# transistor_dc_motor_driver.net
KiCad netlist of a schematic drawn in EAGLE
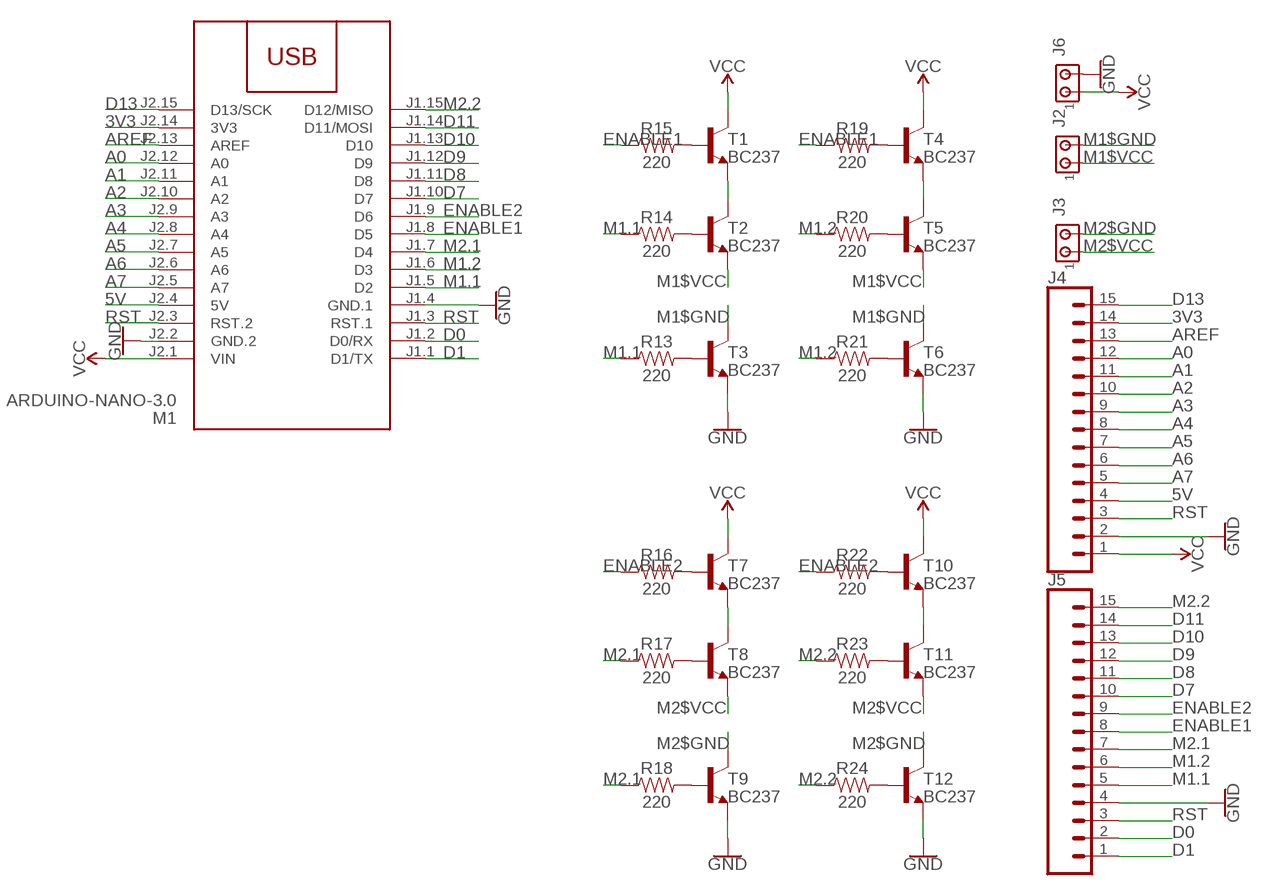
[diagram p0: schematic, sheet 1]

(export (version "E")
  (design (tool "Eeschema 10.0.6"))
  (components
    (comp (ref "J2")
      (value "MTA02-156")
      (footprint "eagle-import:1X2MTA")
      (libsource (lib "eagle-import") (part "MTA02-156"))
    )
    (comp (ref "J3")
      (value "MTA02-156")
      (footprint "eagle-import:1X2MTA")
      (libsource (lib "eagle-import") (part "MTA02-156"))
    )
    (comp (ref "J4")
      (value "CONN_15")
      (footprint "eagle-import:1X15")
      (libsource (lib "eagle-import") (part "CONN_15"))
    )
    (comp (ref "J5")
      (value "CONN_15")
      (footprint "eagle-import:1X15")
      (libsource (lib "eagle-import") (part "CONN_15"))
    )
    (comp (ref "J6")
      (value "MTA02-156")
      (footprint "eagle-import:1X2MTA")
      (libsource (lib "eagle-import") (part "MTA02-156"))
    )
    (comp (ref "M1")
      (value "ARDUINO-NANO-3.0")
      (footprint "eagle-import:ARDUINO-NANO-3.0")
      (libsource (lib "eagle-import") (part "ARDUINO-NANO-3.0"))
    )
    (comp (ref "R13")
      (value "220")
      (footprint "eagle-import:AXIAL-0.3")
      (libsource (lib "eagle-import") (part "1KOHM-HORIZ-1/4W-5%"))
    )
    (comp (ref "R14")
      (value "220")
      (footprint "eagle-import:AXIAL-0.3")
      (libsource (lib "eagle-import") (part "1KOHM-HORIZ-1/4W-5%"))
    )
    (comp (ref "R15")
      (value "220")
      (footprint "eagle-import:AXIAL-0.3")
      (libsource (lib "eagle-import") (part "1KOHM-HORIZ-1/4W-5%"))
    )
    (comp (ref "R16")
      (value "220")
      (footprint "eagle-import:AXIAL-0.3")
      (libsource (lib "eagle-import") (part "1KOHM-HORIZ-1/4W-5%"))
    )
    (comp (ref "R17")
      (value "220")
      (footprint "eagle-import:AXIAL-0.3")
      (libsource (lib "eagle-import") (part "1KOHM-HORIZ-1/4W-5%"))
    )
    (comp (ref "R18")
      (value "220")
      (footprint "eagle-import:AXIAL-0.3")
      (libsource (lib "eagle-import") (part "1KOHM-HORIZ-1/4W-5%"))
    )
    (comp (ref "R19")
      (value "220")
      (footprint "eagle-import:AXIAL-0.3")
      (libsource (lib "eagle-import") (part "1KOHM-HORIZ-1/4W-5%"))
    )
    (comp (ref "R20")
      (value "220")
      (footprint "eagle-import:AXIAL-0.3")
      (libsource (lib "eagle-import") (part "1KOHM-HORIZ-1/4W-5%"))
    )
    (comp (ref "R21")
      (value "220")
      (footprint "eagle-import:AXIAL-0.3")
      (libsource (lib "eagle-import") (part "1KOHM-HORIZ-1/4W-5%"))
    )
    (comp (ref "R22")
      (value "220")
      (footprint "eagle-import:AXIAL-0.3")
      (libsource (lib "eagle-import") (part "1KOHM-HORIZ-1/4W-5%"))
    )
    (comp (ref "R23")
      (value "220")
      (footprint "eagle-import:AXIAL-0.3")
      (libsource (lib "eagle-import") (part "1KOHM-HORIZ-1/4W-5%"))
    )
    (comp (ref "R24")
      (value "220")
      (footprint "eagle-import:AXIAL-0.3")
      (libsource (lib "eagle-import") (part "1KOHM-HORIZ-1/4W-5%"))
    )
    (comp (ref "T1")
      (value "BC237")
      (footprint "eagle-import:TO92")
      (libsource (lib "eagle-import") (part "BC237"))
    )
    (comp (ref "T2")
      (value "BC237")
      (footprint "eagle-import:TO92")
      (libsource (lib "eagle-import") (part "BC237"))
    )
    (comp (ref "T3")
      (value "BC237")
      (footprint "eagle-import:TO92")
      (libsource (lib "eagle-import") (part "BC237"))
    )
    (comp (ref "T4")
      (value "BC237")
      (footprint "eagle-import:TO92")
      (libsource (lib "eagle-import") (part "BC237"))
    )
    (comp (ref "T5")
      (value "BC237")
      (footprint "eagle-import:TO92")
      (libsource (lib "eagle-import") (part "BC237"))
    )
    (comp (ref "T6")
      (value "BC237")
      (footprint "eagle-import:TO92")
      (libsource (lib "eagle-import") (part "BC237"))
    )
    (comp (ref "T7")
      (value "BC237")
      (footprint "eagle-import:TO92")
      (libsource (lib "eagle-import") (part "BC237"))
    )
    (comp (ref "T8")
      (value "BC237")
      (footprint "eagle-import:TO92")
      (libsource (lib "eagle-import") (part "BC237"))
    )
    (comp (ref "T9")
      (value "BC237")
      (footprint "eagle-import:TO92")
      (libsource (lib "eagle-import") (part "BC237"))
    )
    (comp (ref "T10")
      (value "BC237")
      (footprint "eagle-import:TO92")
      (libsource (lib "eagle-import") (part "BC237"))
    )
    (comp (ref "T11")
      (value "BC237")
      (footprint "eagle-import:TO92")
      (libsource (lib "eagle-import") (part "BC237"))
    )
    (comp (ref "T12")
      (value "BC237")
      (footprint "eagle-import:TO92")
      (libsource (lib "eagle-import") (part "BC237"))
    )
  )
  (nets
    (net (code "1") (name "/3V3") (class "Default")
      (node (ref "J4") (pin "14") (pinfunction "14_14") (pintype "passive"))
      (node (ref "M1") (pin "J2.14") (pinfunction "3V3_J2.14") (pintype "power_in"))
    )
    (net (code "2") (name "/5V") (class "Default")
      (node (ref "J4") (pin "4") (pinfunction "4_4") (pintype "passive"))
      (node (ref "M1") (pin "J2.4") (pinfunction "5V_J2.4") (pintype "power_in"))
    )
    (net (code "3") (name "/A0") (class "Default")
      (node (ref "J4") (pin "12") (pinfunction "12_12") (pintype "passive"))
      (node (ref "M1") (pin "J2.12") (pinfunction "A0_J2.12") (pintype "bidirectional"))
    )
    (net (code "4") (name "/A1") (class "Default")
      (node (ref "J4") (pin "11") (pinfunction "11_11") (pintype "passive"))
      (node (ref "M1") (pin "J2.11") (pinfunction "A1_J2.11") (pintype "bidirectional"))
    )
    (net (code "5") (name "/A2") (class "Default")
      (node (ref "J4") (pin "10") (pinfunction "10_10") (pintype "passive"))
      (node (ref "M1") (pin "J2.10") (pinfunction "A2_J2.10") (pintype "bidirectional"))
    )
    (net (code "6") (name "/A3") (class "Default")
      (node (ref "J4") (pin "9") (pinfunction "9_9") (pintype "passive"))
      (node (ref "M1") (pin "J2.9") (pinfunction "A3_J2.9") (pintype "bidirectional"))
    )
    (net (code "7") (name "/A4") (class "Default")
      (node (ref "J4") (pin "8") (pinfunction "8_8") (pintype "passive"))
      (node (ref "M1") (pin "J2.8") (pinfunction "A4_J2.8") (pintype "bidirectional"))
    )
    (net (code "8") (name "/A5") (class "Default")
      (node (ref "J4") (pin "7") (pinfunction "7_7") (pintype "passive"))
      (node (ref "M1") (pin "J2.7") (pinfunction "A5_J2.7") (pintype "bidirectional"))
    )
    (net (code "9") (name "/A6") (class "Default")
      (node (ref "J4") (pin "6") (pinfunction "6_6") (pintype "passive"))
      (node (ref "M1") (pin "J2.6") (pinfunction "A6_J2.6") (pintype "bidirectional"))
    )
    (net (code "10") (name "/A7") (class "Default")
      (node (ref "J4") (pin "5") (pinfunction "5_5") (pintype "passive"))
      (node (ref "M1") (pin "J2.5") (pinfunction "A7_J2.5") (pintype "bidirectional"))
    )
    (net (code "11") (name "/AREF") (class "Default")
      (node (ref "J4") (pin "13") (pinfunction "13_13") (pintype "passive"))
      (node (ref "M1") (pin "J2.13") (pinfunction "AREF_J2.13") (pintype "bidirectional"))
    )
    (net (code "12") (name "/D0") (class "Default")
      (node (ref "J5") (pin "2") (pinfunction "2_2") (pintype "passive"))
      (node (ref "M1") (pin "J1.2") (pinfunction "D0/RX_J1.2") (pintype "bidirectional"))
    )
    (net (code "13") (name "/D1") (class "Default")
      (node (ref "J5") (pin "1") (pinfunction "1_1") (pintype "passive"))
      (node (ref "M1") (pin "J1.1") (pinfunction "D1/TX_J1.1") (pintype "bidirectional"))
    )
    (net (code "14") (name "/D7") (class "Default")
      (node (ref "J5") (pin "10") (pinfunction "10_10") (pintype "passive"))
      (node (ref "M1") (pin "J1.10") (pinfunction "D7_J1.10") (pintype "bidirectional"))
    )
    (net (code "15") (name "/D8") (class "Default")
      (node (ref "J5") (pin "11") (pinfunction "11_11") (pintype "passive"))
      (node (ref "M1") (pin "J1.11") (pinfunction "D8_J1.11") (pintype "bidirectional"))
    )
    (net (code "16") (name "/D9") (class "Default")
      (node (ref "J5") (pin "12") (pinfunction "12_12") (pintype "passive"))
      (node (ref "M1") (pin "J1.12") (pinfunction "D9_J1.12") (pintype "bidirectional"))
    )
    (net (code "17") (name "/D10") (class "Default")
      (node (ref "J5") (pin "13") (pinfunction "13_13") (pintype "passive"))
      (node (ref "M1") (pin "J1.13") (pinfunction "D10_J1.13") (pintype "bidirectional"))
    )
    (net (code "18") (name "/D11") (class "Default")
      (node (ref "J5") (pin "14") (pinfunction "14_14") (pintype "passive"))
      (node (ref "M1") (pin "J1.14") (pinfunction "D11/MOSI_J1.14") (pintype "bidirectional"))
    )
    (net (code "19") (name "/D13") (class "Default")
      (node (ref "J4") (pin "15") (pinfunction "15_15") (pintype "passive"))
      (node (ref "M1") (pin "J2.15") (pinfunction "D13/SCK_J2.15") (pintype "bidirectional"))
    )
    (net (code "20") (name "/ENABLE1") (class "Default")
      (node (ref "J5") (pin "8") (pinfunction "8_8") (pintype "passive"))
      (node (ref "M1") (pin "J1.8") (pinfunction "D5_J1.8") (pintype "bidirectional"))
      (node (ref "R15") (pin "P$1") (pinfunction "1_P$1") (pintype "passive"))
      (node (ref "R19") (pin "P$1") (pinfunction "1_P$1") (pintype "passive"))
    )
    (net (code "21") (name "/ENABLE2") (class "Default")
      (node (ref "J5") (pin "9") (pinfunction "9_9") (pintype "passive"))
      (node (ref "M1") (pin "J1.9") (pinfunction "D6_J1.9") (pintype "bidirectional"))
      (node (ref "R16") (pin "P$1") (pinfunction "1_P$1") (pintype "passive"))
      (node (ref "R22") (pin "P$1") (pinfunction "1_P$1") (pintype "passive"))
    )
    (net (code "22") (name "/M1$GND") (class "Default")
      (node (ref "J2") (pin "2") (pinfunction "2_2") (pintype "passive"))
      (node (ref "T3") (pin "3") (pinfunction "C_3") (pintype "passive"))
      (node (ref "T6") (pin "3") (pinfunction "C_3") (pintype "passive"))
    )
    (net (code "23") (name "/M1$VCC") (class "Default")
      (node (ref "J2") (pin "1") (pinfunction "1_1") (pintype "passive"))
      (node (ref "T2") (pin "1") (pinfunction "E_1") (pintype "passive"))
      (node (ref "T5") (pin "1") (pinfunction "E_1") (pintype "passive"))
    )
    (net (code "24") (name "/M1.1") (class "Default")
      (node (ref "J5") (pin "5") (pinfunction "5_5") (pintype "passive"))
      (node (ref "M1") (pin "J1.5") (pinfunction "D2_J1.5") (pintype "bidirectional"))
      (node (ref "R13") (pin "P$1") (pinfunction "1_P$1") (pintype "passive"))
      (node (ref "R14") (pin "P$1") (pinfunction "1_P$1") (pintype "passive"))
    )
    (net (code "25") (name "/M1.2") (class "Default")
      (node (ref "J5") (pin "6") (pinfunction "6_6") (pintype "passive"))
      (node (ref "M1") (pin "J1.6") (pinfunction "D3_J1.6") (pintype "bidirectional"))
      (node (ref "R20") (pin "P$1") (pinfunction "1_P$1") (pintype "passive"))
      (node (ref "R21") (pin "P$1") (pinfunction "1_P$1") (pintype "passive"))
    )
    (net (code "26") (name "/M2$GND") (class "Default")
      (node (ref "J3") (pin "2") (pinfunction "2_2") (pintype "passive"))
      (node (ref "T12") (pin "3") (pinfunction "C_3") (pintype "passive"))
      (node (ref "T9") (pin "3") (pinfunction "C_3") (pintype "passive"))
    )
    (net (code "27") (name "/M2$VCC") (class "Default")
      (node (ref "J3") (pin "1") (pinfunction "1_1") (pintype "passive"))
      (node (ref "T11") (pin "1") (pinfunction "E_1") (pintype "passive"))
      (node (ref "T8") (pin "1") (pinfunction "E_1") (pintype "passive"))
    )
    (net (code "28") (name "/M2.1") (class "Default")
      (node (ref "J5") (pin "7") (pinfunction "7_7") (pintype "passive"))
      (node (ref "M1") (pin "J1.7") (pinfunction "D4_J1.7") (pintype "bidirectional"))
      (node (ref "R17") (pin "P$1") (pinfunction "1_P$1") (pintype "passive"))
      (node (ref "R18") (pin "P$1") (pinfunction "1_P$1") (pintype "passive"))
    )
    (net (code "29") (name "/M2.2") (class "Default")
      (node (ref "J5") (pin "15") (pinfunction "15_15") (pintype "passive"))
      (node (ref "M1") (pin "J1.15") (pinfunction "D12/MISO_J1.15") (pintype "bidirectional"))
      (node (ref "R23") (pin "P$1") (pinfunction "1_P$1") (pintype "passive"))
      (node (ref "R24") (pin "P$1") (pinfunction "1_P$1") (pintype "passive"))
    )
    (net (code "30") (name "/RST") (class "Default")
      (node (ref "J4") (pin "3") (pinfunction "3_3") (pintype "passive"))
      (node (ref "J5") (pin "3") (pinfunction "3_3") (pintype "passive"))
      (node (ref "M1") (pin "J1.3") (pinfunction "RST.1_J1.3") (pintype "bidirectional"))
      (node (ref "M1") (pin "J2.3") (pinfunction "RST.2_J2.3") (pintype "bidirectional"))
    )
    (net (code "31") (name "GND") (class "Default")
      (node (ref "J4") (pin "2") (pinfunction "2_2") (pintype "passive"))
      (node (ref "J5") (pin "4") (pinfunction "4_4") (pintype "passive"))
      (node (ref "J6") (pin "2") (pinfunction "2_2") (pintype "passive"))
      (node (ref "M1") (pin "J1.4") (pinfunction "GND.1_J1.4") (pintype "power_in"))
      (node (ref "M1") (pin "J2.2") (pinfunction "GND.2_J2.2") (pintype "power_in"))
      (node (ref "T12") (pin "1") (pinfunction "E_1") (pintype "passive"))
      (node (ref "T3") (pin "1") (pinfunction "E_1") (pintype "passive"))
      (node (ref "T6") (pin "1") (pinfunction "E_1") (pintype "passive"))
      (node (ref "T9") (pin "1") (pinfunction "E_1") (pintype "passive"))
    )
    (net (code "32") (name "Net-(R13-2)") (class "Default")
      (node (ref "R13") (pin "P$2") (pinfunction "2_P$2") (pintype "passive"))
      (node (ref "T3") (pin "2") (pinfunction "B_2") (pintype "passive"))
    )
    (net (code "33") (name "Net-(R14-2)") (class "Default")
      (node (ref "R14") (pin "P$2") (pinfunction "2_P$2") (pintype "passive"))
      (node (ref "T2") (pin "2") (pinfunction "B_2") (pintype "passive"))
    )
    (net (code "34") (name "Net-(R15-2)") (class "Default")
      (node (ref "R15") (pin "P$2") (pinfunction "2_P$2") (pintype "passive"))
      (node (ref "T1") (pin "2") (pinfunction "B_2") (pintype "passive"))
    )
    (net (code "35") (name "Net-(R16-2)") (class "Default")
      (node (ref "R16") (pin "P$2") (pinfunction "2_P$2") (pintype "passive"))
      (node (ref "T7") (pin "2") (pinfunction "B_2") (pintype "passive"))
    )
    (net (code "36") (name "Net-(R17-2)") (class "Default")
      (node (ref "R17") (pin "P$2") (pinfunction "2_P$2") (pintype "passive"))
      (node (ref "T8") (pin "2") (pinfunction "B_2") (pintype "passive"))
    )
    (net (code "37") (name "Net-(R18-2)") (class "Default")
      (node (ref "R18") (pin "P$2") (pinfunction "2_P$2") (pintype "passive"))
      (node (ref "T9") (pin "2") (pinfunction "B_2") (pintype "passive"))
    )
    (net (code "38") (name "Net-(R19-2)") (class "Default")
      (node (ref "R19") (pin "P$2") (pinfunction "2_P$2") (pintype "passive"))
      (node (ref "T4") (pin "2") (pinfunction "B_2") (pintype "passive"))
    )
    (net (code "39") (name "Net-(R20-2)") (class "Default")
      (node (ref "R20") (pin "P$2") (pinfunction "2_P$2") (pintype "passive"))
      (node (ref "T5") (pin "2") (pinfunction "B_2") (pintype "passive"))
    )
    (net (code "40") (name "Net-(R21-2)") (class "Default")
      (node (ref "R21") (pin "P$2") (pinfunction "2_P$2") (pintype "passive"))
      (node (ref "T6") (pin "2") (pinfunction "B_2") (pintype "passive"))
    )
    (net (code "41") (name "Net-(R22-2)") (class "Default")
      (node (ref "R22") (pin "P$2") (pinfunction "2_P$2") (pintype "passive"))
      (node (ref "T10") (pin "2") (pinfunction "B_2") (pintype "passive"))
    )
    (net (code "42") (name "Net-(R23-2)") (class "Default")
      (node (ref "R23") (pin "P$2") (pinfunction "2_P$2") (pintype "passive"))
      (node (ref "T11") (pin "2") (pinfunction "B_2") (pintype "passive"))
    )
    (net (code "43") (name "Net-(R24-2)") (class "Default")
      (node (ref "R24") (pin "P$2") (pinfunction "2_P$2") (pintype "passive"))
      (node (ref "T12") (pin "2") (pinfunction "B_2") (pintype "passive"))
    )
    (net (code "44") (name "Net-(T1-E)") (class "Default")
      (node (ref "T1") (pin "1") (pinfunction "E_1") (pintype "passive"))
      (node (ref "T2") (pin "3") (pinfunction "C_3") (pintype "passive"))
    )
    (net (code "45") (name "Net-(T4-E)") (class "Default")
      (node (ref "T4") (pin "1") (pinfunction "E_1") (pintype "passive"))
      (node (ref "T5") (pin "3") (pinfunction "C_3") (pintype "passive"))
    )
    (net (code "46") (name "Net-(T7-E)") (class "Default")
      (node (ref "T7") (pin "1") (pinfunction "E_1") (pintype "passive"))
      (node (ref "T8") (pin "3") (pinfunction "C_3") (pintype "passive"))
    )
    (net (code "47") (name "Net-(T10-E)") (class "Default")
      (node (ref "T10") (pin "1") (pinfunction "E_1") (pintype "passive"))
      (node (ref "T11") (pin "3") (pinfunction "C_3") (pintype "passive"))
    )
    (net (code "48") (name "VCC") (class "Default")
      (node (ref "J4") (pin "1") (pinfunction "1_1") (pintype "passive"))
      (node (ref "J6") (pin "1") (pinfunction "1_1") (pintype "passive"))
      (node (ref "M1") (pin "J2.1") (pinfunction "VIN_J2.1") (pintype "power_in"))
      (node (ref "T1") (pin "3") (pinfunction "C_3") (pintype "passive"))
      (node (ref "T10") (pin "3") (pinfunction "C_3") (pintype "passive"))
      (node (ref "T4") (pin "3") (pinfunction "C_3") (pintype "passive"))
      (node (ref "T7") (pin "3") (pinfunction "C_3") (pintype "passive"))
    )
  )
)
